# IDD_measurement.net
KiCad netlist of a schematic drawn in Altium Designer
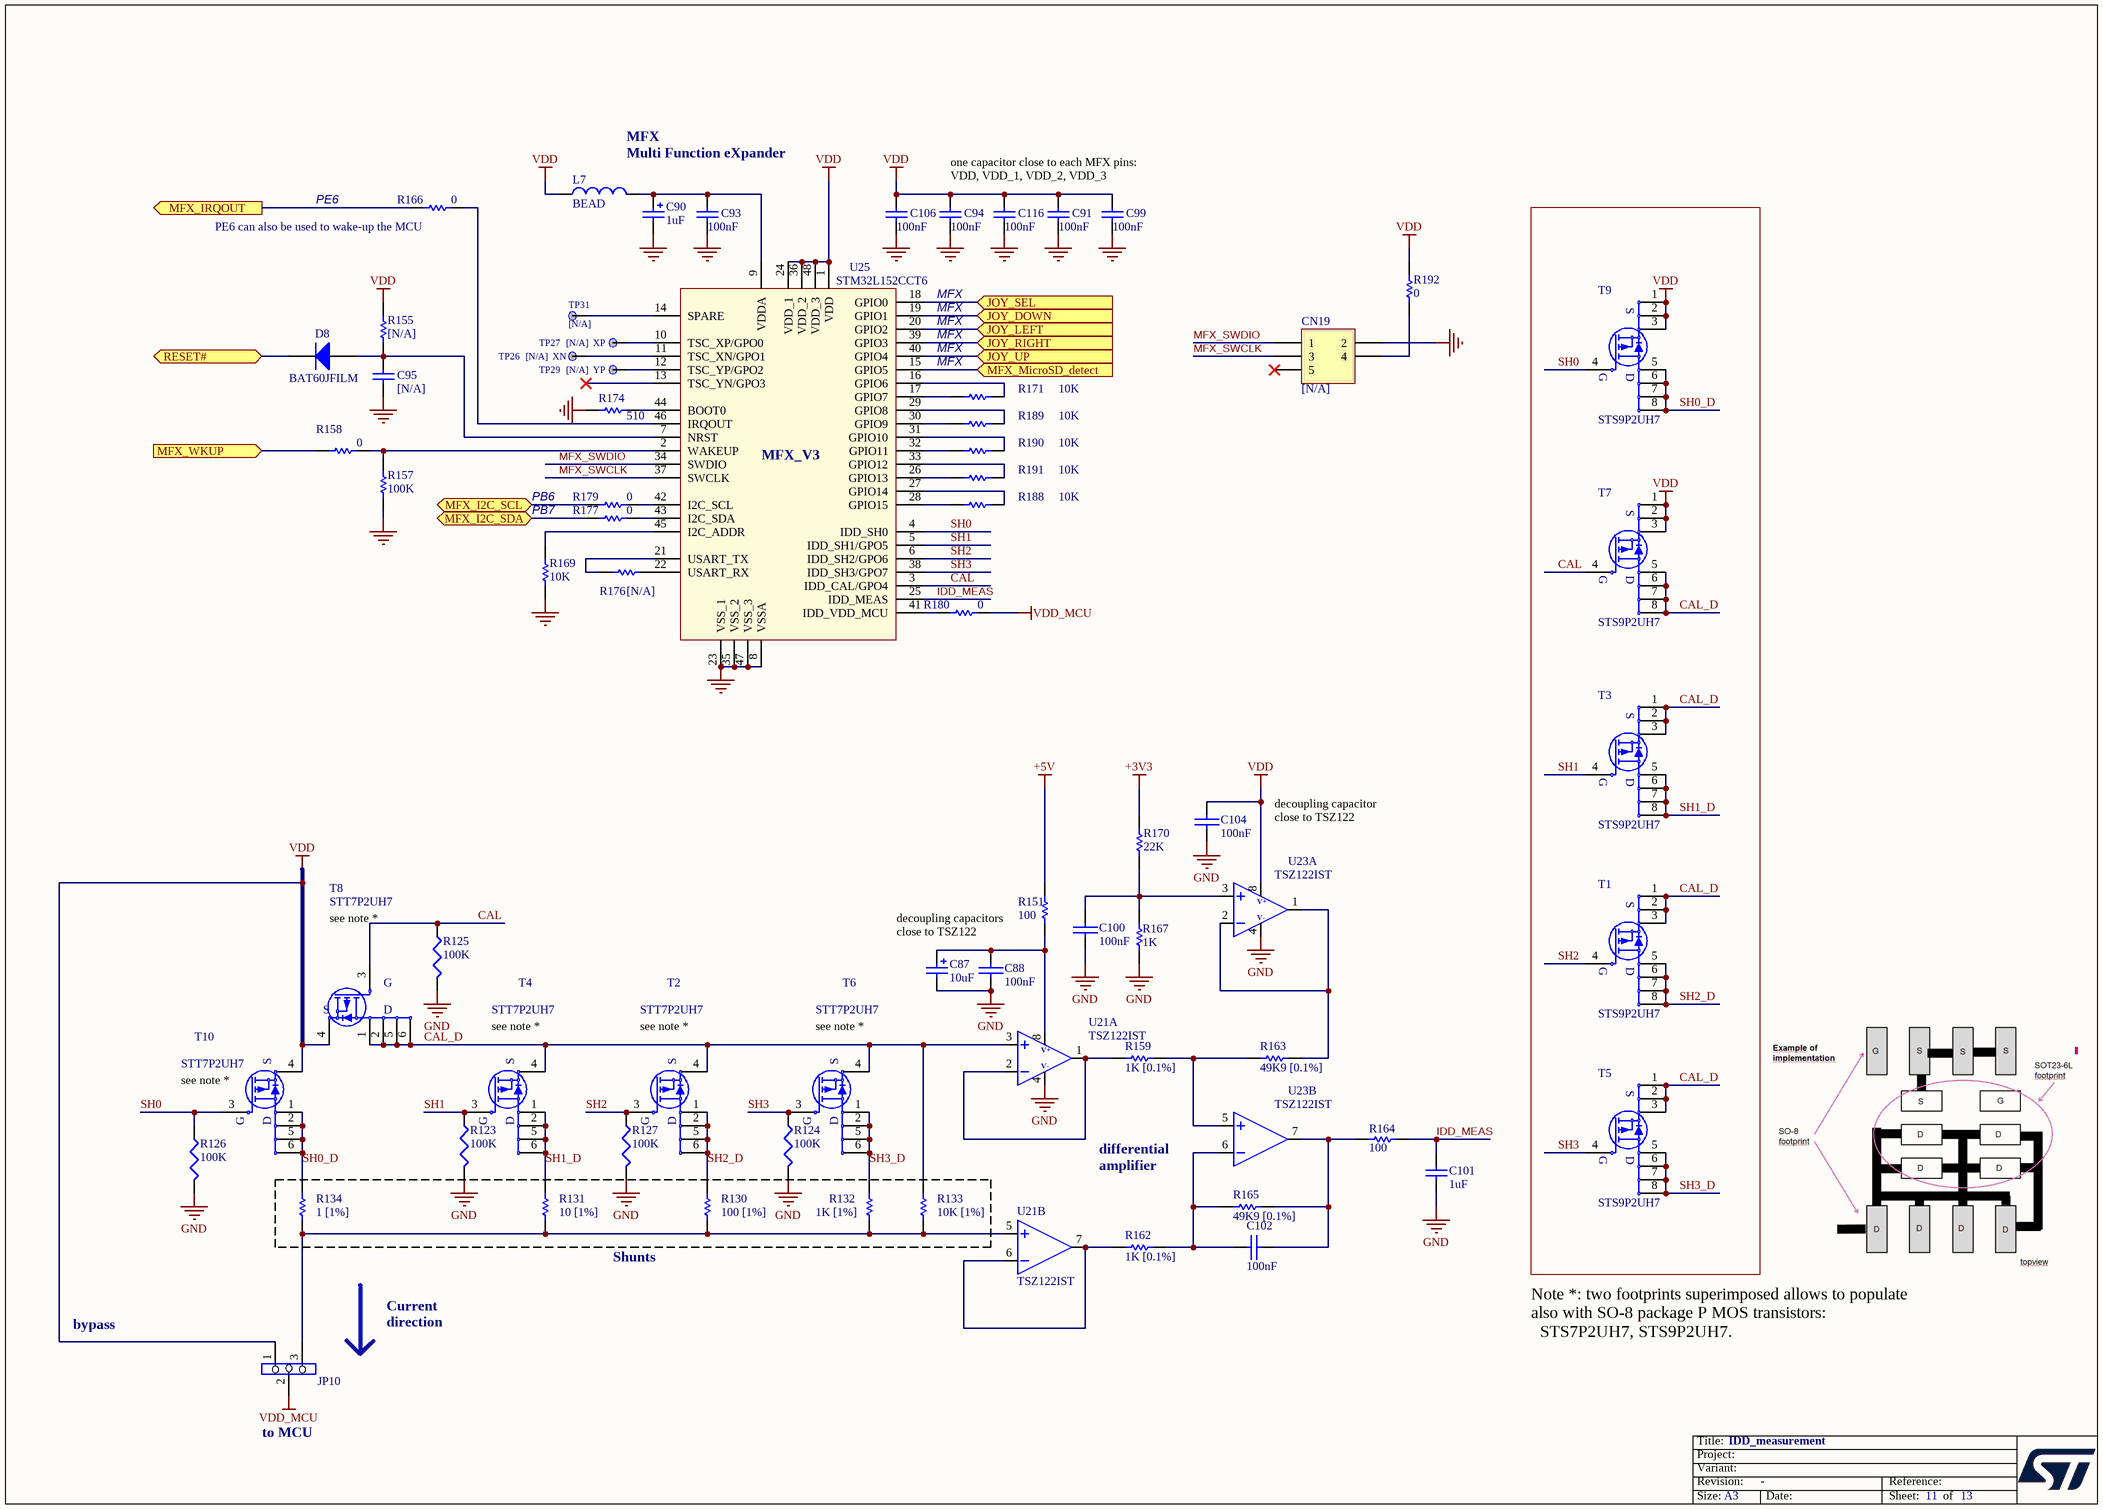
[diagram p0: IDD_measurement.SchDoc]

(export (version "E")
  (design (tool "Eeschema 10.0.6"))
  (components
    (comp (ref "C87")
      (value "10uF")
      (footprint "TAN-A")
      (description "Polarized Capacitor (Radial)")
      (fields (field (name "PUBLISHER") "Altium Limited"))
      (libsource (lib "Miscellaneous Devices") (part "Cap Pol1"))
    )
    (comp (ref "C88") (value "100nF") (footprint "0402C") (libsource (lib "*") (part "CAP")))
    (comp (ref "C90")
      (value "1uF")
      (footprint "TAN-A")
      (description "Polarized Capacitor")
      (libsource (lib "MCD_TOOLS") (part "Cap_1uF_POL_10%_TANA"))
    )
    (comp (ref "C91")
      (value "100nF")
      (footprint "0402C")
      (description "Capacitor,100nF,16V,X7R,10%,0402,YAGEO")
      (libsource (lib "MCD_TOOLS") (part "Cap_100nF_X7R_10%_0402"))
    )
    (comp (ref "C93")
      (value "100nF")
      (footprint "0402C")
      (description "Capacitor,100nF,16V,X7R,10%,0402,YAGEO")
      (libsource (lib "MCD_TOOLS") (part "Cap_100nF_X7R_10%_0402"))
    )
    (comp (ref "C94")
      (value "100nF")
      (footprint "0402C")
      (description "Capacitor,100nF,16V,X7R,10%,0402,YAGEO")
      (libsource (lib "MCD_TOOLS") (part "Cap_100nF_X7R_10%_0402"))
    )
    (comp (ref "C95")
      (value "[N/A]")
      (footprint "0603C")
      (description "Capacitor")
      (fields (field (name "PUBLISHER") "Altium Limited"))
      (libsource (lib "Miscellaneous Devices") (part "cap"))
    )
    (comp (ref "C99")
      (value "100nF")
      (footprint "0402C")
      (description "Capacitor,100nF,16V,X7R,10%,0402,YAGEO")
      (libsource (lib "MCD_TOOLS") (part "Cap_100nF_X7R_10%_0402"))
    )
    (comp (ref "C100") (value "100nF") (footprint "0402C") (libsource (lib "*") (part "CAP")))
    (comp (ref "C101")
      (value "1uF")
      (footprint "0603C")
      (description "Capacitor")
      (fields (field (name "PUBLISHER") "Altium Limited"))
      (libsource (lib "Miscellaneous Devices") (part "CAP"))
    )
    (comp (ref "C102") (value "100nF") (footprint "0402C") (libsource (lib "*") (part "CAP")))
    (comp (ref "C104") (value "100nF") (footprint "0402C") (libsource (lib "*") (part "CAP")))
    (comp (ref "C106")
      (value "100nF")
      (footprint "0402C")
      (description "Capacitor,100nF,16V,X7R,10%,0402,YAGEO")
      (libsource (lib "MCD_TOOLS") (part "Cap_100nF_X7R_10%_0402"))
    )
    (comp (ref "C116")
      (value "100nF")
      (footprint "0402C")
      (description "Capacitor,100nF,16V,X7R,10%,0402,YAGEO")
      (libsource (lib "MCD_TOOLS") (part "Cap_100nF_X7R_10%_0402"))
    )
    (comp (ref "CN19")
      (value "[N/A]")
      (footprint "HDR_2X3-1_2R54-6")
      (description "Header, 3-Pin, Dual row")
      (fields (field (name "PUBLISHER") "Altium Limited"))
      (libsource (lib "Miscellaneous Connectors") (part "Header 3X2"))
    )
    (comp (ref "D8")
      (value "BAT60JFILM")
      (footprint "SOD-323")
      (description "Default Diode")
      (fields (field (name "PUBLISHER") "Altium Limited"))
      (libsource (lib "MB1144_1") (part "Diode"))
    )
    (comp (ref "JP10") (value "~") (footprint "SIP3") (libsource (lib "STR910_SCHLIB") (part "Jumper3")))
    (comp (ref "L7")
      (value "BEAD")
      (footprint "0603L")
      (description "Bead,600R,350mA,0603")
      (libsource (lib "MCD_TOOLS") (part "BEAD_600R_350MA_0603"))
    )
    (comp (ref "R123")
      (value "100K")
      (footprint "0402R")
      (description "Resistor")
      (libsource (lib "*") (part "RES1"))
    )
    (comp (ref "R124")
      (value "100K")
      (footprint "0402R")
      (description "Resistor")
      (libsource (lib "*") (part "RES1"))
    )
    (comp (ref "R125")
      (value "100K")
      (footprint "0402R")
      (description "Resistor")
      (libsource (lib "*") (part "RES1"))
    )
    (comp (ref "R126")
      (value "100K")
      (footprint "0402R")
      (description "Resistor")
      (libsource (lib "*") (part "RES1"))
    )
    (comp (ref "R127")
      (value "100K")
      (footprint "0402R")
      (description "Resistor")
      (libsource (lib "*") (part "RES1"))
    )
    (comp (ref "R130")
      (value "100 [1%]")
      (footprint "0603R")
      (description "Resistor")
      (fields (field (name "PUBLISHER") "Altium Limited"))
      (libsource (lib "Miscellaneous Devices") (part "res1"))
    )
    (comp (ref "R131")
      (value "10 [1%]")
      (footprint "0603R")
      (description "Resistor")
      (fields (field (name "PUBLISHER") "Altium Limited"))
      (libsource (lib "Miscellaneous Devices") (part "res1"))
    )
    (comp (ref "R132")
      (value "1K [1%]")
      (footprint "0603R")
      (description "Resistor")
      (fields (field (name "PUBLISHER") "Altium Limited"))
      (libsource (lib "Miscellaneous Devices") (part "res1"))
    )
    (comp (ref "R133")
      (value "10K [1%]")
      (footprint "0603R")
      (description "Resistor")
      (fields (field (name "PUBLISHER") "Altium Limited"))
      (libsource (lib "Miscellaneous Devices") (part "res1"))
    )
    (comp (ref "R134")
      (value "1 [1%]")
      (footprint "0603R")
      (description "Resistor")
      (fields (field (name "PUBLISHER") "Altium Limited"))
      (libsource (lib "Miscellaneous Devices") (part "res1"))
    )
    (comp (ref "R151")
      (value "100")
      (footprint "0402R")
      (description "Resistor")
      (fields (field (name "PUBLISHER") "Altium Limited"))
      (libsource (lib "Miscellaneous Devices") (part "res1"))
    )
    (comp (ref "R155")
      (value "[N/A]")
      (footprint "0603R")
      (description "Resistor")
      (fields (field (name "PUBLISHER") "Altium Limited"))
      (libsource (lib "Miscellaneous Devices") (part "Res1"))
    )
    (comp (ref "R157")
      (value "100K")
      (footprint "0402R")
      (description "Resistor 0402 / 0603 / 0805")
      (libsource (lib "MCD_TOOLS") (part "Resistor_ST"))
    )
    (comp (ref "R158")
      (value "0")
      (footprint "0603R")
      (description "Resistor")
      (fields (field (name "PUBLISHER") "Altium Limited"))
      (libsource (lib "Miscellaneous Devices") (part "Res1"))
    )
    (comp (ref "R159")
      (value "1K [0.1%]")
      (footprint "0603R")
      (description "Resistor")
      (fields (field (name "PUBLISHER") "Altium Limited"))
      (libsource (lib "Miscellaneous Devices") (part "res1"))
    )
    (comp (ref "R162")
      (value "1K [0.1%]")
      (footprint "0603R")
      (description "Resistor")
      (fields (field (name "PUBLISHER") "Altium Limited"))
      (libsource (lib "Miscellaneous Devices") (part "res1"))
    )
    (comp (ref "R163")
      (value "49K9 [0.1%]")
      (footprint "0603R")
      (description "Resistor")
      (fields (field (name "PUBLISHER") "Altium Limited"))
      (libsource (lib "Miscellaneous Devices") (part "res1"))
    )
    (comp (ref "R164")
      (value "100")
      (footprint "0402R")
      (description "Resistor")
      (fields (field (name "PUBLISHER") "Altium Limited"))
      (libsource (lib "Miscellaneous Devices") (part "Res1"))
    )
    (comp (ref "R165")
      (value "49K9 [0.1%]")
      (footprint "0603R")
      (description "Resistor")
      (fields (field (name "PUBLISHER") "Altium Limited"))
      (libsource (lib "Miscellaneous Devices") (part "res1"))
    )
    (comp (ref "R166")
      (value "0")
      (footprint "0603R")
      (description "Resistor")
      (fields (field (name "PUBLISHER") "Altium Limited"))
      (libsource (lib "Miscellaneous Devices") (part "Res1"))
    )
    (comp (ref "R167")
      (value "1K")
      (footprint "0402R")
      (description "Resistor")
      (fields (field (name "PUBLISHER") "Altium Limited"))
      (libsource (lib "Miscellaneous Devices") (part "Res1"))
    )
    (comp (ref "R169")
      (value "10K")
      (footprint "0603R")
      (description "Resistor")
      (fields (field (name "PUBLISHER") "Altium Limited"))
      (libsource (lib "Miscellaneous Devices") (part "res1"))
    )
    (comp (ref "R170")
      (value "22K")
      (footprint "0603R")
      (description "Resistor")
      (fields (field (name "PUBLISHER") "Altium Limited"))
      (libsource (lib "Miscellaneous Devices") (part "res1"))
    )
    (comp (ref "R171")
      (value "10K")
      (footprint "0603R")
      (description "Resistor")
      (fields (field (name "PUBLISHER") "Altium Limited"))
      (libsource (lib "Miscellaneous Devices") (part "res1"))
    )
    (comp (ref "R174")
      (value "510")
      (footprint "0402R")
      (description "Resistor 0402 / 0603 / 0805")
      (libsource (lib "MCD_TOOLS") (part "Resistor_ST"))
    )
    (comp (ref "R176")
      (value "[N/A]")
      (footprint "0603R")
      (description "Resistor")
      (fields (field (name "PUBLISHER") "Altium Limited"))
      (libsource (lib "Miscellaneous Devices") (part "res1"))
    )
    (comp (ref "R177")
      (value "0")
      (footprint "0603R")
      (description "Resistor")
      (fields (field (name "PUBLISHER") "Altium Limited"))
      (libsource (lib "Miscellaneous Devices") (part "Res1"))
    )
    (comp (ref "R179")
      (value "0")
      (footprint "0603R")
      (description "Resistor")
      (fields (field (name "PUBLISHER") "Altium Limited"))
      (libsource (lib "Miscellaneous Devices") (part "Res1"))
    )
    (comp (ref "R180")
      (value "0")
      (footprint "0603R")
      (description "Resistor")
      (fields (field (name "PUBLISHER") "Altium Limited"))
      (libsource (lib "Miscellaneous Devices") (part "Res1"))
    )
    (comp (ref "R188")
      (value "10K")
      (footprint "0603R")
      (description "Resistor")
      (fields (field (name "PUBLISHER") "Altium Limited"))
      (libsource (lib "Miscellaneous Devices") (part "res1"))
    )
    (comp (ref "R189")
      (value "10K")
      (footprint "0603R")
      (description "Resistor")
      (fields (field (name "PUBLISHER") "Altium Limited"))
      (libsource (lib "Miscellaneous Devices") (part "res1"))
    )
    (comp (ref "R190")
      (value "10K")
      (footprint "0603R")
      (description "Resistor")
      (fields (field (name "PUBLISHER") "Altium Limited"))
      (libsource (lib "Miscellaneous Devices") (part "res1"))
    )
    (comp (ref "R191")
      (value "10K")
      (footprint "0603R")
      (description "Resistor")
      (fields (field (name "PUBLISHER") "Altium Limited"))
      (libsource (lib "Miscellaneous Devices") (part "res1"))
    )
    (comp (ref "R192")
      (value "0")
      (footprint "0603R")
      (description "Resistor")
      (fields (field (name "PUBLISHER") "Altium Limited"))
      (libsource (lib "Miscellaneous Devices") (part "Res1"))
    )
    (comp (ref "T1")
      (value "STS9P2UH7")
      (footprint "SOIC8_1R27_4R9X6")
      (description "STripFET VII Power MOSFET, P-CHANNEL 20V - 0.023 - 7A - SO-8")
      (libsource (lib "MCD_TOOLS") (part "STS7P2UH7"))
    )
    (comp (ref "T2")
      (value "STT7P2UH7")
      (footprint "SOT23-6L")
      (description "STripFET VII DeepGATE Power MOSFET, P-CHANNEL 20 V, 0.0146, 7 A - SOT23-6L")
      (libsource (lib "MCD_TOOLS") (part "STT7P2UH7"))
    )
    (comp (ref "T3")
      (value "STS9P2UH7")
      (footprint "SOIC8_1R27_4R9X6")
      (description "STripFET VII Power MOSFET, P-CHANNEL 20V - 0.023 - 7A - SO-8")
      (libsource (lib "MCD_TOOLS") (part "STS7P2UH7"))
    )
    (comp (ref "T4")
      (value "STT7P2UH7")
      (footprint "SOT23-6L")
      (description "STripFET VII DeepGATE Power MOSFET, P-CHANNEL 20 V, 0.0146, 7 A - SOT23-6L")
      (libsource (lib "MCD_TOOLS") (part "STT7P2UH7"))
    )
    (comp (ref "T5")
      (value "STS9P2UH7")
      (footprint "SOIC8_1R27_4R9X6")
      (description "STripFET VII Power MOSFET, P-CHANNEL 20V - 0.023 - 7A - SO-8")
      (libsource (lib "MCD_TOOLS") (part "STS7P2UH7"))
    )
    (comp (ref "T6")
      (value "STT7P2UH7")
      (footprint "SOT23-6L")
      (description "STripFET VII DeepGATE Power MOSFET, P-CHANNEL 20 V, 0.0146, 7 A - SOT23-6L")
      (libsource (lib "MCD_TOOLS") (part "STT7P2UH7"))
    )
    (comp (ref "T7")
      (value "STS9P2UH7")
      (footprint "SOIC8_1R27_4R9X6")
      (description "STripFET VII Power MOSFET, P-CHANNEL 20V - 0.023 - 7A - SO-8")
      (libsource (lib "MCD_TOOLS") (part "STS7P2UH7"))
    )
    (comp (ref "T8")
      (value "STT7P2UH7")
      (footprint "SOT23-6L")
      (description "STripFET VII DeepGATE Power MOSFET, P-CHANNEL 20 V, 0.0146, 7 A - SOT23-6L")
      (libsource (lib "MCD_TOOLS") (part "STT7P2UH7"))
    )
    (comp (ref "T9")
      (value "STS9P2UH7")
      (footprint "SOIC8_1R27_4R9X6")
      (description "STripFET VII Power MOSFET, P-CHANNEL 20V - 0.023 - 7A - SO-8")
      (libsource (lib "MCD_TOOLS") (part "STS7P2UH7"))
    )
    (comp (ref "T10")
      (value "STT7P2UH7")
      (footprint "SOT23-6L")
      (description "STripFET VII DeepGATE Power MOSFET, P-CHANNEL 20 V, 0.0146, 7 A - SOT23-6L")
      (libsource (lib "MCD_TOOLS") (part "STT7P2UH7"))
    )
    (comp (ref "TP26")
      (value "[N/A]")
      (footprint "TP")
      (fields (field (name "SILKSCREEN") "XN"))
      (libsource (lib "*") (part "TP"))
    )
    (comp (ref "TP27")
      (value "[N/A]")
      (footprint "TP")
      (fields (field (name "SILKSCREEN") "XP"))
      (libsource (lib "*") (part "TP"))
    )
    (comp (ref "TP29")
      (value "[N/A]")
      (footprint "TP")
      (fields (field (name "SILKSCREEN") "YP"))
      (libsource (lib "*") (part "TP"))
    )
    (comp (ref "TP31") (value "[N/A]") (footprint "TP") (libsource (lib "*") (part "TP")))
    (comp (ref "U21")
      (value "TSZ122IST")
      (footprint "MSOP8_0R65_3X4R9")
      (libsource (lib "Lib_stella") (part "AOP-8PINS"))
    )
    (comp (ref "U23")
      (value "TSZ122IST")
      (footprint "MSOP8_0R65_3X4R9")
      (libsource (lib "Lib_stella") (part "AOP-8PINS"))
    )
    (comp (ref "U25")
      (value "STM32L152CCT6")
      (footprint "LQFP48_0R5_9X9")
      (description "Multifunction expander")
      (libsource (lib "MB1168_1") (part "MFX_V3"))
    )
  )
  (nets
    (net (code "1") (name "+3V3") (class "Default")
      (node (ref "R170") (pin "1") (pinfunction "1_1") (pintype "passive"))
    )
    (net (code "2") (name "+5V") (class "Default")
      (node (ref "R151") (pin "1") (pinfunction "1_1") (pintype "passive"))
    )
    (net (code "3") (name "/CAL") (class "Default")
      (node (ref "R125") (pin "1") (pinfunction "1_1") (pintype "passive"))
      (node (ref "T7") (pin "4") (pinfunction "G_4") (pintype "passive"))
      (node (ref "T8") (pin "3") (pinfunction "G_3") (pintype "passive"))
      (node (ref "U25") (pin "3") (pinfunction "IDD_CAL/GPO4_3") (pintype "passive"))
    )
    (net (code "4") (name "/CAL_D") (class "Default")
      (node (ref "R133") (pin "2") (pinfunction "2_2") (pintype "passive"))
      (node (ref "T1") (pin "1") (pinfunction "S_1") (pintype "passive"))
      (node (ref "T1") (pin "2") (pinfunction "S_2") (pintype "passive"))
      (node (ref "T1") (pin "3") (pinfunction "S_3") (pintype "passive"))
      (node (ref "T2") (pin "4") (pinfunction "S_4") (pintype "passive"))
      (node (ref "T3") (pin "1") (pinfunction "S_1") (pintype "passive"))
      (node (ref "T3") (pin "2") (pinfunction "S_2") (pintype "passive"))
      (node (ref "T3") (pin "3") (pinfunction "S_3") (pintype "passive"))
      (node (ref "T4") (pin "4") (pinfunction "S_4") (pintype "passive"))
      (node (ref "T5") (pin "1") (pinfunction "S_1") (pintype "passive"))
      (node (ref "T5") (pin "2") (pinfunction "S_2") (pintype "passive"))
      (node (ref "T5") (pin "3") (pinfunction "S_3") (pintype "passive"))
      (node (ref "T6") (pin "4") (pinfunction "S_4") (pintype "passive"))
      (node (ref "T7") (pin "5") (pinfunction "D_5") (pintype "passive"))
      (node (ref "T7") (pin "6") (pinfunction "D_6") (pintype "passive"))
      (node (ref "T7") (pin "7") (pinfunction "D_7") (pintype "passive"))
      (node (ref "T7") (pin "8") (pinfunction "D_8") (pintype "passive"))
      (node (ref "T8") (pin "1") (pinfunction "S_1") (pintype "passive"))
      (node (ref "T8") (pin "2") (pinfunction "S_2") (pintype "passive"))
      (node (ref "T8") (pin "5") (pinfunction "D_5") (pintype "passive"))
      (node (ref "T8") (pin "6") (pinfunction "D_6") (pintype "passive"))
      (node (ref "U21") (pin "3") (pintype "passive"))
    )
    (net (code "5") (name "/IDD_MEAS") (class "Default")
      (node (ref "C101") (pin "2") (pinfunction "2_2") (pintype "passive"))
      (node (ref "R164") (pin "1") (pinfunction "1_1") (pintype "passive"))
      (node (ref "U25") (pin "25") (pinfunction "IDD_MEAS_25") (pintype "passive"))
    )
    (net (code "6") (name "/JOY_DOWN") (class "Default")
      (node (ref "U25") (pin "19") (pinfunction "GPIO1_19") (pintype "passive"))
    )
    (net (code "7") (name "/JOY_LEFT") (class "Default")
      (node (ref "U25") (pin "20") (pinfunction "GPIO2_20") (pintype "passive"))
    )
    (net (code "8") (name "/JOY_RIGHT") (class "Default")
      (node (ref "U25") (pin "39") (pinfunction "GPIO3_39") (pintype "passive"))
    )
    (net (code "9") (name "/JOY_SEL") (class "Default")
      (node (ref "U25") (pin "18") (pinfunction "GPIO0_18") (pintype "passive"))
    )
    (net (code "10") (name "/JOY_UP") (class "Default")
      (node (ref "U25") (pin "40") (pinfunction "GPIO4_40") (pintype "passive"))
    )
    (net (code "11") (name "/MFX_I2C_SCL") (class "Default")
      (node (ref "R179") (pin "1") (pinfunction "1_1") (pintype "passive"))
    )
    (net (code "12") (name "/MFX_I2C_SDA") (class "Default")
      (node (ref "R177") (pin "1") (pinfunction "1_1") (pintype "passive"))
    )
    (net (code "13") (name "/MFX_IRQOUT") (class "Default")
      (node (ref "R166") (pin "1") (pinfunction "1_1") (pintype "passive"))
    )
    (net (code "14") (name "/MFX_MicroSD_detect") (class "Default")
      (node (ref "U25") (pin "15") (pinfunction "GPIO5_15") (pintype "passive"))
    )
    (net (code "15") (name "/MFX_SWCLK") (class "Default")
      (node (ref "CN19") (pin "3") (pinfunction "3_3") (pintype "passive"))
      (node (ref "U25") (pin "37") (pinfunction "SWCLK_37") (pintype "passive"))
    )
    (net (code "16") (name "/MFX_SWDIO") (class "Default")
      (node (ref "CN19") (pin "1") (pinfunction "1_1") (pintype "passive"))
      (node (ref "U25") (pin "34") (pinfunction "SWDIO_34") (pintype "passive"))
    )
    (net (code "17") (name "/MFX_WKUP") (class "Default")
      (node (ref "R158") (pin "1") (pinfunction "1_1") (pintype "passive"))
    )
    (net (code "18") (name "/RESET#") (class "Default")
      (node (ref "D8") (pin "2") (pinfunction "K_2") (pintype "passive"))
    )
    (net (code "19") (name "/SH0") (class "Default")
      (node (ref "R126") (pin "1") (pinfunction "1_1") (pintype "passive"))
      (node (ref "T10") (pin "3") (pinfunction "G_3") (pintype "passive"))
      (node (ref "T9") (pin "4") (pinfunction "G_4") (pintype "passive"))
      (node (ref "U25") (pin "4") (pinfunction "IDD_SH0_4") (pintype "passive"))
    )
    (net (code "20") (name "/SH0_D") (class "Default")
      (node (ref "R134") (pin "2") (pinfunction "2_2") (pintype "passive"))
      (node (ref "T10") (pin "1") (pinfunction "S_1") (pintype "passive"))
      (node (ref "T10") (pin "2") (pinfunction "S_2") (pintype "passive"))
      (node (ref "T10") (pin "5") (pinfunction "D_5") (pintype "passive"))
      (node (ref "T10") (pin "6") (pinfunction "D_6") (pintype "passive"))
      (node (ref "T9") (pin "5") (pinfunction "D_5") (pintype "passive"))
      (node (ref "T9") (pin "6") (pinfunction "D_6") (pintype "passive"))
      (node (ref "T9") (pin "7") (pinfunction "D_7") (pintype "passive"))
      (node (ref "T9") (pin "8") (pinfunction "D_8") (pintype "passive"))
    )
    (net (code "21") (name "/SH1") (class "Default")
      (node (ref "R123") (pin "1") (pinfunction "1_1") (pintype "passive"))
      (node (ref "T3") (pin "4") (pinfunction "G_4") (pintype "passive"))
      (node (ref "T4") (pin "3") (pinfunction "G_3") (pintype "passive"))
      (node (ref "U25") (pin "5") (pinfunction "IDD_SH1/GPO5_5") (pintype "passive"))
    )
    (net (code "22") (name "/SH1_D") (class "Default")
      (node (ref "R131") (pin "2") (pinfunction "2_2") (pintype "passive"))
      (node (ref "T3") (pin "5") (pinfunction "D_5") (pintype "passive"))
      (node (ref "T3") (pin "6") (pinfunction "D_6") (pintype "passive"))
      (node (ref "T3") (pin "7") (pinfunction "D_7") (pintype "passive"))
      (node (ref "T3") (pin "8") (pinfunction "D_8") (pintype "passive"))
      (node (ref "T4") (pin "1") (pinfunction "S_1") (pintype "passive"))
      (node (ref "T4") (pin "2") (pinfunction "S_2") (pintype "passive"))
      (node (ref "T4") (pin "5") (pinfunction "D_5") (pintype "passive"))
      (node (ref "T4") (pin "6") (pinfunction "D_6") (pintype "passive"))
    )
    (net (code "23") (name "/SH2") (class "Default")
      (node (ref "R127") (pin "1") (pinfunction "1_1") (pintype "passive"))
      (node (ref "T1") (pin "4") (pinfunction "G_4") (pintype "passive"))
      (node (ref "T2") (pin "3") (pinfunction "G_3") (pintype "passive"))
      (node (ref "U25") (pin "6") (pinfunction "IDD_SH2/GPO6_6") (pintype "passive"))
    )
    (net (code "24") (name "/SH2_D") (class "Default")
      (node (ref "R130") (pin "2") (pinfunction "2_2") (pintype "passive"))
      (node (ref "T1") (pin "5") (pinfunction "D_5") (pintype "passive"))
      (node (ref "T1") (pin "6") (pinfunction "D_6") (pintype "passive"))
      (node (ref "T1") (pin "7") (pinfunction "D_7") (pintype "passive"))
      (node (ref "T1") (pin "8") (pinfunction "D_8") (pintype "passive"))
      (node (ref "T2") (pin "1") (pinfunction "S_1") (pintype "passive"))
      (node (ref "T2") (pin "2") (pinfunction "S_2") (pintype "passive"))
      (node (ref "T2") (pin "5") (pinfunction "D_5") (pintype "passive"))
      (node (ref "T2") (pin "6") (pinfunction "D_6") (pintype "passive"))
    )
    (net (code "25") (name "/SH3") (class "Default")
      (node (ref "R124") (pin "1") (pinfunction "1_1") (pintype "passive"))
      (node (ref "T5") (pin "4") (pinfunction "G_4") (pintype "passive"))
      (node (ref "T6") (pin "3") (pinfunction "G_3") (pintype "passive"))
      (node (ref "U25") (pin "38") (pinfunction "IDD_SH3/GPO7_38") (pintype "passive"))
    )
    (net (code "26") (name "/SH3_D") (class "Default")
      (node (ref "R132") (pin "2") (pinfunction "2_2") (pintype "passive"))
      (node (ref "T5") (pin "5") (pinfunction "D_5") (pintype "passive"))
      (node (ref "T5") (pin "6") (pinfunction "D_6") (pintype "passive"))
      (node (ref "T5") (pin "7") (pinfunction "D_7") (pintype "passive"))
      (node (ref "T5") (pin "8") (pinfunction "D_8") (pintype "passive"))
      (node (ref "T6") (pin "1") (pinfunction "S_1") (pintype "passive"))
      (node (ref "T6") (pin "2") (pinfunction "S_2") (pintype "passive"))
      (node (ref "T6") (pin "5") (pinfunction "D_5") (pintype "passive"))
      (node (ref "T6") (pin "6") (pinfunction "D_6") (pintype "passive"))
    )
    (net (code "27") (name "GND") (class "Default")
      (node (ref "C100") (pin "2") (pinfunction "2_2") (pintype "passive"))
      (node (ref "C101") (pin "1") (pinfunction "1_1") (pintype "passive"))
      (node (ref "C104") (pin "2") (pinfunction "2_2") (pintype "passive"))
      (node (ref "C106") (pin "1") (pinfunction "1_1") (pintype "passive"))
      (node (ref "C116") (pin "2") (pinfunction "2_2") (pintype "passive"))
      (node (ref "C87") (pin "2") (pinfunction "2_2") (pintype "passive"))
      (node (ref "C88") (pin "2") (pinfunction "2_2") (pintype "passive"))
      (node (ref "C90") (pin "2") (pinfunction "2_2") (pintype "passive"))
      (node (ref "C91") (pin "1") (pinfunction "1_1") (pintype "passive"))
      (node (ref "C93") (pin "1") (pinfunction "1_1") (pintype "passive"))
      (node (ref "C94") (pin "1") (pinfunction "1_1") (pintype "passive"))
      (node (ref "C95") (pin "1") (pinfunction "1_1") (pintype "passive"))
      (node (ref "C99") (pin "1") (pinfunction "1_1") (pintype "passive"))
      (node (ref "CN19") (pin "2") (pinfunction "2_2") (pintype "passive"))
      (node (ref "R123") (pin "2") (pinfunction "2_2") (pintype "passive"))
      (node (ref "R124") (pin "2") (pinfunction "2_2") (pintype "passive"))
      (node (ref "R125") (pin "2") (pinfunction "2_2") (pintype "passive"))
      (node (ref "R126") (pin "2") (pinfunction "2_2") (pintype "passive"))
      (node (ref "R127") (pin "2") (pinfunction "2_2") (pintype "passive"))
      (node (ref "R157") (pin "2") (pinfunction "2_2") (pintype "passive"))
      (node (ref "R167") (pin "2") (pinfunction "2_2") (pintype "passive"))
      (node (ref "R169") (pin "1") (pinfunction "1_1") (pintype "passive"))
      (node (ref "R174") (pin "2") (pinfunction "2_2") (pintype "passive"))
      (node (ref "U21") (pin "4") (pintype "passive"))
      (node (ref "U23") (pin "4") (pintype "passive"))
      (node (ref "U25") (pin "23") (pinfunction "VSS_1_23") (pintype "passive"))
      (node (ref "U25") (pin "35") (pinfunction "VSS_2_35") (pintype "passive"))
      (node (ref "U25") (pin "47") (pinfunction "VSS_3_47") (pintype "passive"))
      (node (ref "U25") (pin "8") (pinfunction "VSSA_8") (pintype "passive"))
    )
    (net (code "28") (name "Net-(C87-Pad1)") (class "Default")
      (node (ref "C87") (pin "1") (pinfunction "1_1") (pintype "passive"))
      (node (ref "C88") (pin "1") (pinfunction "1_1") (pintype "passive"))
      (node (ref "R151") (pin "2") (pinfunction "2_2") (pintype "passive"))
      (node (ref "U21") (pin "8") (pintype "passive"))
    )
    (net (code "29") (name "Net-(C100-Pad1)") (class "Default")
      (node (ref "C100") (pin "1") (pinfunction "1_1") (pintype "passive"))
      (node (ref "R167") (pin "1") (pinfunction "1_1") (pintype "passive"))
      (node (ref "R170") (pin "2") (pinfunction "2_2") (pintype "passive"))
      (node (ref "U23") (pin "3") (pintype "passive"))
    )
    (net (code "30") (name "Net-(C102-Pad1)") (class "Default")
      (node (ref "C102") (pin "1") (pinfunction "1_1") (pintype "passive"))
      (node (ref "R162") (pin "2") (pinfunction "2_2") (pintype "passive"))
      (node (ref "R165") (pin "1") (pinfunction "1_1") (pintype "passive"))
      (node (ref "U23") (pin "6") (pintype "passive"))
    )
    (net (code "31") (name "Net-(C102-Pad2)") (class "Default")
      (node (ref "C102") (pin "2") (pinfunction "2_2") (pintype "passive"))
      (node (ref "R164") (pin "2") (pinfunction "2_2") (pintype "passive"))
      (node (ref "R165") (pin "2") (pinfunction "2_2") (pintype "passive"))
      (node (ref "U23") (pin "7") (pintype "passive"))
    )
    (net (code "32") (name "Net-(CN19-Pad4)") (class "Default")
      (node (ref "CN19") (pin "4") (pinfunction "4_4") (pintype "passive"))
      (node (ref "R192") (pin "1") (pinfunction "1_1") (pintype "passive"))
    )
    (net (code "33") (name "Net-(D8-A)") (class "Default")
      (node (ref "C95") (pin "2") (pinfunction "2_2") (pintype "passive"))
      (node (ref "D8") (pin "1") (pinfunction "A_1") (pintype "passive"))
      (node (ref "R155") (pin "2") (pinfunction "2_2") (pintype "passive"))
      (node (ref "U25") (pin "7") (pinfunction "NRST_7") (pintype "passive"))
    )
    (net (code "34") (name "Net-(JP10-Pad3)") (class "Default")
      (node (ref "JP10") (pin "3") (pintype "passive"))
      (node (ref "R130") (pin "1") (pinfunction "1_1") (pintype "passive"))
      (node (ref "R131") (pin "1") (pinfunction "1_1") (pintype "passive"))
      (node (ref "R132") (pin "1") (pinfunction "1_1") (pintype "passive"))
      (node (ref "R133") (pin "1") (pinfunction "1_1") (pintype "passive"))
      (node (ref "R134") (pin "1") (pinfunction "1_1") (pintype "passive"))
      (node (ref "U21") (pin "5") (pintype "passive"))
    )
    (net (code "35") (name "Net-(R159-Pad1)") (class "Default")
      (node (ref "R159") (pin "1") (pinfunction "1_1") (pintype "passive"))
      (node (ref "U21") (pin "1") (pintype "passive"))
      (node (ref "U21") (pin "2") (pintype "passive"))
    )
    (net (code "36") (name "Net-(R159-Pad2)") (class "Default")
      (node (ref "R159") (pin "2") (pinfunction "2_2") (pintype "passive"))
      (node (ref "R163") (pin "1") (pinfunction "1_1") (pintype "passive"))
      (node (ref "U23") (pin "5") (pintype "passive"))
    )
    (net (code "37") (name "Net-(R162-Pad1)") (class "Default")
      (node (ref "R162") (pin "1") (pinfunction "1_1") (pintype "passive"))
      (node (ref "U21") (pin "6") (pintype "passive"))
      (node (ref "U21") (pin "7") (pintype "passive"))
    )
    (net (code "38") (name "Net-(R163-Pad2)") (class "Default")
      (node (ref "R163") (pin "2") (pinfunction "2_2") (pintype "passive"))
      (node (ref "U23") (pin "1") (pintype "passive"))
      (node (ref "U23") (pin "2") (pintype "passive"))
    )
    (net (code "39") (name "Net-(U25-BOOT0)") (class "Default")
      (node (ref "R174") (pin "1") (pinfunction "1_1") (pintype "passive"))
      (node (ref "U25") (pin "44") (pinfunction "BOOT0_44") (pintype "passive"))
    )
    (net (code "40") (name "Net-(U25-GPIO6)") (class "Default")
      (node (ref "R171") (pin "2") (pinfunction "2_2") (pintype "passive"))
      (node (ref "U25") (pin "16") (pinfunction "GPIO6_16") (pintype "passive"))
    )
    (net (code "41") (name "Net-(U25-GPIO7)") (class "Default")
      (node (ref "R171") (pin "1") (pinfunction "1_1") (pintype "passive"))
      (node (ref "U25") (pin "17") (pinfunction "GPIO7_17") (pintype "passive"))
    )
    (net (code "42") (name "Net-(U25-GPIO8)") (class "Default")
      (node (ref "R189") (pin "2") (pinfunction "2_2") (pintype "passive"))
      (node (ref "U25") (pin "29") (pinfunction "GPIO8_29") (pintype "passive"))
    )
    (net (code "43") (name "Net-(U25-GPIO9)") (class "Default")
      (node (ref "R189") (pin "1") (pinfunction "1_1") (pintype "passive"))
      (node (ref "U25") (pin "30") (pinfunction "GPIO9_30") (pintype "passive"))
    )
    (net (code "44") (name "Net-(U25-GPIO10)") (class "Default")
      (node (ref "R190") (pin "2") (pinfunction "2_2") (pintype "passive"))
      (node (ref "U25") (pin "31") (pinfunction "GPIO10_31") (pintype "passive"))
    )
    (net (code "45") (name "Net-(U25-GPIO11)") (class "Default")
      (node (ref "R190") (pin "1") (pinfunction "1_1") (pintype "passive"))
      (node (ref "U25") (pin "32") (pinfunction "GPIO11_32") (pintype "passive"))
    )
    (net (code "46") (name "Net-(U25-GPIO12)") (class "Default")
      (node (ref "R191") (pin "2") (pinfunction "2_2") (pintype "passive"))
      (node (ref "U25") (pin "33") (pinfunction "GPIO12_33") (pintype "passive"))
    )
    (net (code "47") (name "Net-(U25-GPIO13)") (class "Default")
      (node (ref "R191") (pin "1") (pinfunction "1_1") (pintype "passive"))
      (node (ref "U25") (pin "26") (pinfunction "GPIO13_26") (pintype "passive"))
    )
    (net (code "48") (name "Net-(U25-GPIO14)") (class "Default")
      (node (ref "R188") (pin "2") (pinfunction "2_2") (pintype "passive"))
      (node (ref "U25") (pin "27") (pinfunction "GPIO14_27") (pintype "passive"))
    )
    (net (code "49") (name "Net-(U25-GPIO15)") (class "Default")
      (node (ref "R188") (pin "1") (pinfunction "1_1") (pintype "passive"))
      (node (ref "U25") (pin "28") (pinfunction "GPIO15_28") (pintype "passive"))
    )
    (net (code "50") (name "Net-(U25-I2C_ADDR)") (class "Default")
      (node (ref "R169") (pin "2") (pinfunction "2_2") (pintype "passive"))
      (node (ref "U25") (pin "45") (pinfunction "I2C_ADDR_45") (pintype "passive"))
    )
    (net (code "51") (name "Net-(U25-I2C_SCL)") (class "Default")
      (node (ref "R179") (pin "2") (pinfunction "2_2") (pintype "passive"))
      (node (ref "U25") (pin "42") (pinfunction "I2C_SCL_42") (pintype "passive"))
    )
    (net (code "52") (name "Net-(U25-I2C_SDA)") (class "Default")
      (node (ref "R177") (pin "2") (pinfunction "2_2") (pintype "passive"))
      (node (ref "U25") (pin "43") (pinfunction "I2C_SDA_43") (pintype "passive"))
    )
    (net (code "53") (name "Net-(U25-IDD_VDD_MCU)") (class "Default")
      (node (ref "R180") (pin "1") (pinfunction "1_1") (pintype "passive"))
      (node (ref "U25") (pin "41") (pinfunction "IDD_VDD_MCU_41") (pintype "passive"))
    )
    (net (code "54") (name "Net-(U25-IRQOUT)") (class "Default")
      (node (ref "R166") (pin "2") (pinfunction "2_2") (pintype "passive"))
      (node (ref "U25") (pin "46") (pinfunction "IRQOUT_46") (pintype "passive"))
    )
    (net (code "55") (name "Net-(U25-SPARE)") (class "Default")
      (node (ref "TP31") (pin "1") (pinfunction "1_1") (pintype "passive"))
      (node (ref "U25") (pin "14") (pinfunction "SPARE_14") (pintype "passive"))
    )
    (net (code "56") (name "Net-(U25-TSC_XN{slash}GPO1)") (class "Default")
      (node (ref "TP26") (pin "1") (pinfunction "1_1") (pintype "passive"))
      (node (ref "U25") (pin "11") (pinfunction "TSC_XN/GPO1_11") (pintype "passive"))
    )
    (net (code "57") (name "Net-(U25-TSC_XP{slash}GPO0)") (class "Default")
      (node (ref "TP27") (pin "1") (pinfunction "1_1") (pintype "passive"))
      (node (ref "U25") (pin "10") (pinfunction "TSC_XP/GPO0_10") (pintype "passive"))
    )
    (net (code "58") (name "Net-(U25-TSC_YP{slash}GPO2)") (class "Default")
      (node (ref "TP29") (pin "1") (pinfunction "1_1") (pintype "passive"))
      (node (ref "U25") (pin "12") (pinfunction "TSC_YP/GPO2_12") (pintype "passive"))
    )
    (net (code "59") (name "Net-(U25-USART_RX)") (class "Default")
      (node (ref "R176") (pin "2") (pinfunction "2_2") (pintype "passive"))
      (node (ref "U25") (pin "22") (pinfunction "USART_RX_22") (pintype "passive"))
    )
    (net (code "60") (name "Net-(U25-USART_TX)") (class "Default")
      (node (ref "R176") (pin "1") (pinfunction "1_1") (pintype "passive"))
      (node (ref "U25") (pin "21") (pinfunction "USART_TX_21") (pintype "passive"))
    )
    (net (code "61") (name "Net-(U25-VDDA)") (class "Default")
      (node (ref "C90") (pin "1") (pinfunction "1_1") (pintype "passive"))
      (node (ref "C93") (pin "2") (pinfunction "2_2") (pintype "passive"))
      (node (ref "L7") (pin "2") (pinfunction "2_2") (pintype "passive"))
      (node (ref "U25") (pin "9") (pinfunction "VDDA_9") (pintype "passive"))
    )
    (net (code "62") (name "Net-(U25-WAKEUP)") (class "Default")
      (node (ref "R157") (pin "1") (pinfunction "1_1") (pintype "passive"))
      (node (ref "R158") (pin "2") (pinfunction "2_2") (pintype "passive"))
      (node (ref "U25") (pin "2") (pinfunction "WAKEUP_2") (pintype "passive"))
    )
    (net (code "63") (name "VDD") (class "Default")
      (node (ref "C104") (pin "1") (pinfunction "1_1") (pintype "passive"))
      (node (ref "C106") (pin "2") (pinfunction "2_2") (pintype "passive"))
      (node (ref "C116") (pin "1") (pinfunction "1_1") (pintype "passive"))
      (node (ref "C91") (pin "2") (pinfunction "2_2") (pintype "passive"))
      (node (ref "C94") (pin "2") (pinfunction "2_2") (pintype "passive"))
      (node (ref "C99") (pin "2") (pinfunction "2_2") (pintype "passive"))
      (node (ref "JP10") (pin "1") (pintype "passive"))
      (node (ref "L7") (pin "1") (pinfunction "1_1") (pintype "passive"))
      (node (ref "R155") (pin "1") (pinfunction "1_1") (pintype "passive"))
      (node (ref "R192") (pin "2") (pinfunction "2_2") (pintype "passive"))
      (node (ref "T10") (pin "4") (pinfunction "S_4") (pintype "passive"))
      (node (ref "T7") (pin "1") (pinfunction "S_1") (pintype "passive"))
      (node (ref "T7") (pin "2") (pinfunction "S_2") (pintype "passive"))
      (node (ref "T7") (pin "3") (pinfunction "S_3") (pintype "passive"))
      (node (ref "T8") (pin "4") (pinfunction "S_4") (pintype "passive"))
      (node (ref "T9") (pin "1") (pinfunction "S_1") (pintype "passive"))
      (node (ref "T9") (pin "2") (pinfunction "S_2") (pintype "passive"))
      (node (ref "T9") (pin "3") (pinfunction "S_3") (pintype "passive"))
      (node (ref "U23") (pin "8") (pintype "passive"))
      (node (ref "U25") (pin "1") (pinfunction "VDD_1") (pintype "passive"))
      (node (ref "U25") (pin "24") (pinfunction "VDD_1_24") (pintype "passive"))
      (node (ref "U25") (pin "36") (pinfunction "VDD_2_36") (pintype "passive"))
      (node (ref "U25") (pin "48") (pinfunction "VDD_3_48") (pintype "passive"))
    )
    (net (code "64") (name "VDD_MCU") (class "Default")
      (node (ref "JP10") (pin "2") (pintype "passive"))
      (node (ref "R180") (pin "2") (pinfunction "2_2") (pintype "passive"))
    )
    (net (code "65") (name "unconnected-(CN19-Pad5)") (class "Default")
      (node (ref "CN19") (pin "5") (pinfunction "5_5") (pintype "passive+no_connect"))
    )
    (net (code "66") (name "unconnected-(U25-TSC_YN{slash}GPO3-Pad13)") (class "Default")
      (node (ref "U25") (pin "13") (pinfunction "TSC_YN/GPO3_13") (pintype "passive+no_connect"))
    )
  )
)
